# power.net
KiCad netlist of a schematic drawn in EAGLE
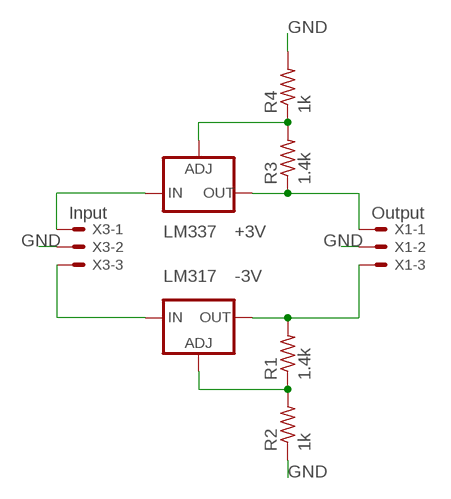
[diagram p0: schematic, sheet 1]

(export (version "E")
  (design (tool "Eeschema 10.0.6"))
  (components
    (comp (ref "LM317")
      (value "-3V")
      (footprint "eagle-import:317TL")
      (libsource (lib "eagle-import") (part "LM317TL"))
    )
    (comp (ref "LM337")
      (value "+3V")
      (footprint "eagle-import:337TL")
      (libsource (lib "eagle-import") (part "LM337TL"))
    )
    (comp (ref "R1")
      (value "1.4k")
      (footprint "eagle-import:0204_7")
      (libsource (lib "eagle-import") (part "R-US_0204/7"))
    )
    (comp (ref "R2")
      (value "1k")
      (footprint "eagle-import:0204_7")
      (libsource (lib "eagle-import") (part "R-US_0204/7"))
    )
    (comp (ref "R3")
      (value "1.4k")
      (footprint "eagle-import:0204_7")
      (libsource (lib "eagle-import") (part "R-US_0204/7"))
    )
    (comp (ref "R4")
      (value "1k")
      (footprint "eagle-import:0204_7")
      (libsource (lib "eagle-import") (part "R-US_0204/7"))
    )
    (comp (ref "X1")
      (value "Output")
      (footprint "eagle-import:22-23-2031")
      (fields (field (name "MF") "MOLEX") (field (name "MPN") "22-23-2031"))
      (libsource (lib "eagle-import") (part "22-23-2031"))
    )
    (comp (ref "X3")
      (value "Input")
      (footprint "eagle-import:22-23-2031")
      (fields (field (name "MF") "MOLEX") (field (name "MPN") "22-23-2031"))
      (libsource (lib "eagle-import") (part "22-23-2031"))
    )
  )
  (nets
    (net (code "1") (name "/GND") (class "Default")
      (node (ref "R2") (pin "1") (pinfunction "1_1") (pintype "passive"))
      (node (ref "R4") (pin "2") (pinfunction "2_2") (pintype "passive"))
      (node (ref "X1") (pin "2") (pinfunction "S_2") (pintype "passive"))
      (node (ref "X3") (pin "2") (pinfunction "S_2") (pintype "passive"))
    )
    (net (code "2") (name "Net-(LM317-ADJ)") (class "Default")
      (node (ref "LM317") (pin "1") (pinfunction "ADJ_1") (pintype "input"))
      (node (ref "R1") (pin "1") (pinfunction "1_1") (pintype "passive"))
      (node (ref "R2") (pin "2") (pinfunction "2_2") (pintype "passive"))
    )
    (net (code "3") (name "Net-(LM317-IN)") (class "Default")
      (node (ref "LM317") (pin "3") (pinfunction "IN_3") (pintype "input"))
      (node (ref "X3") (pin "3") (pinfunction "S_3") (pintype "passive"))
    )
    (net (code "4") (name "Net-(LM317-OUT)") (class "Default")
      (node (ref "LM317") (pin "2") (pinfunction "OUT_2") (pintype "passive"))
      (node (ref "R1") (pin "2") (pinfunction "2_2") (pintype "passive"))
      (node (ref "X1") (pin "3") (pinfunction "S_3") (pintype "passive"))
    )
    (net (code "5") (name "Net-(LM337-ADJ)") (class "Default")
      (node (ref "LM337") (pin "1") (pinfunction "ADJ_1") (pintype "input"))
      (node (ref "R3") (pin "2") (pinfunction "2_2") (pintype "passive"))
      (node (ref "R4") (pin "1") (pinfunction "1_1") (pintype "passive"))
    )
    (net (code "6") (name "Net-(LM337-IN)") (class "Default")
      (node (ref "LM337") (pin "2") (pinfunction "IN_2") (pintype "input"))
      (node (ref "X3") (pin "1") (pinfunction "S_1") (pintype "passive"))
    )
    (net (code "7") (name "Net-(LM337-OUT)") (class "Default")
      (node (ref "LM337") (pin "3") (pinfunction "OUT_3") (pintype "passive"))
      (node (ref "R3") (pin "1") (pinfunction "1_1") (pintype "passive"))
      (node (ref "X1") (pin "1") (pinfunction "S_1") (pintype "passive"))
    )
  )
)
